# BeoModern_schemat.net
KiCad netlist of a schematic drawn in EAGLE
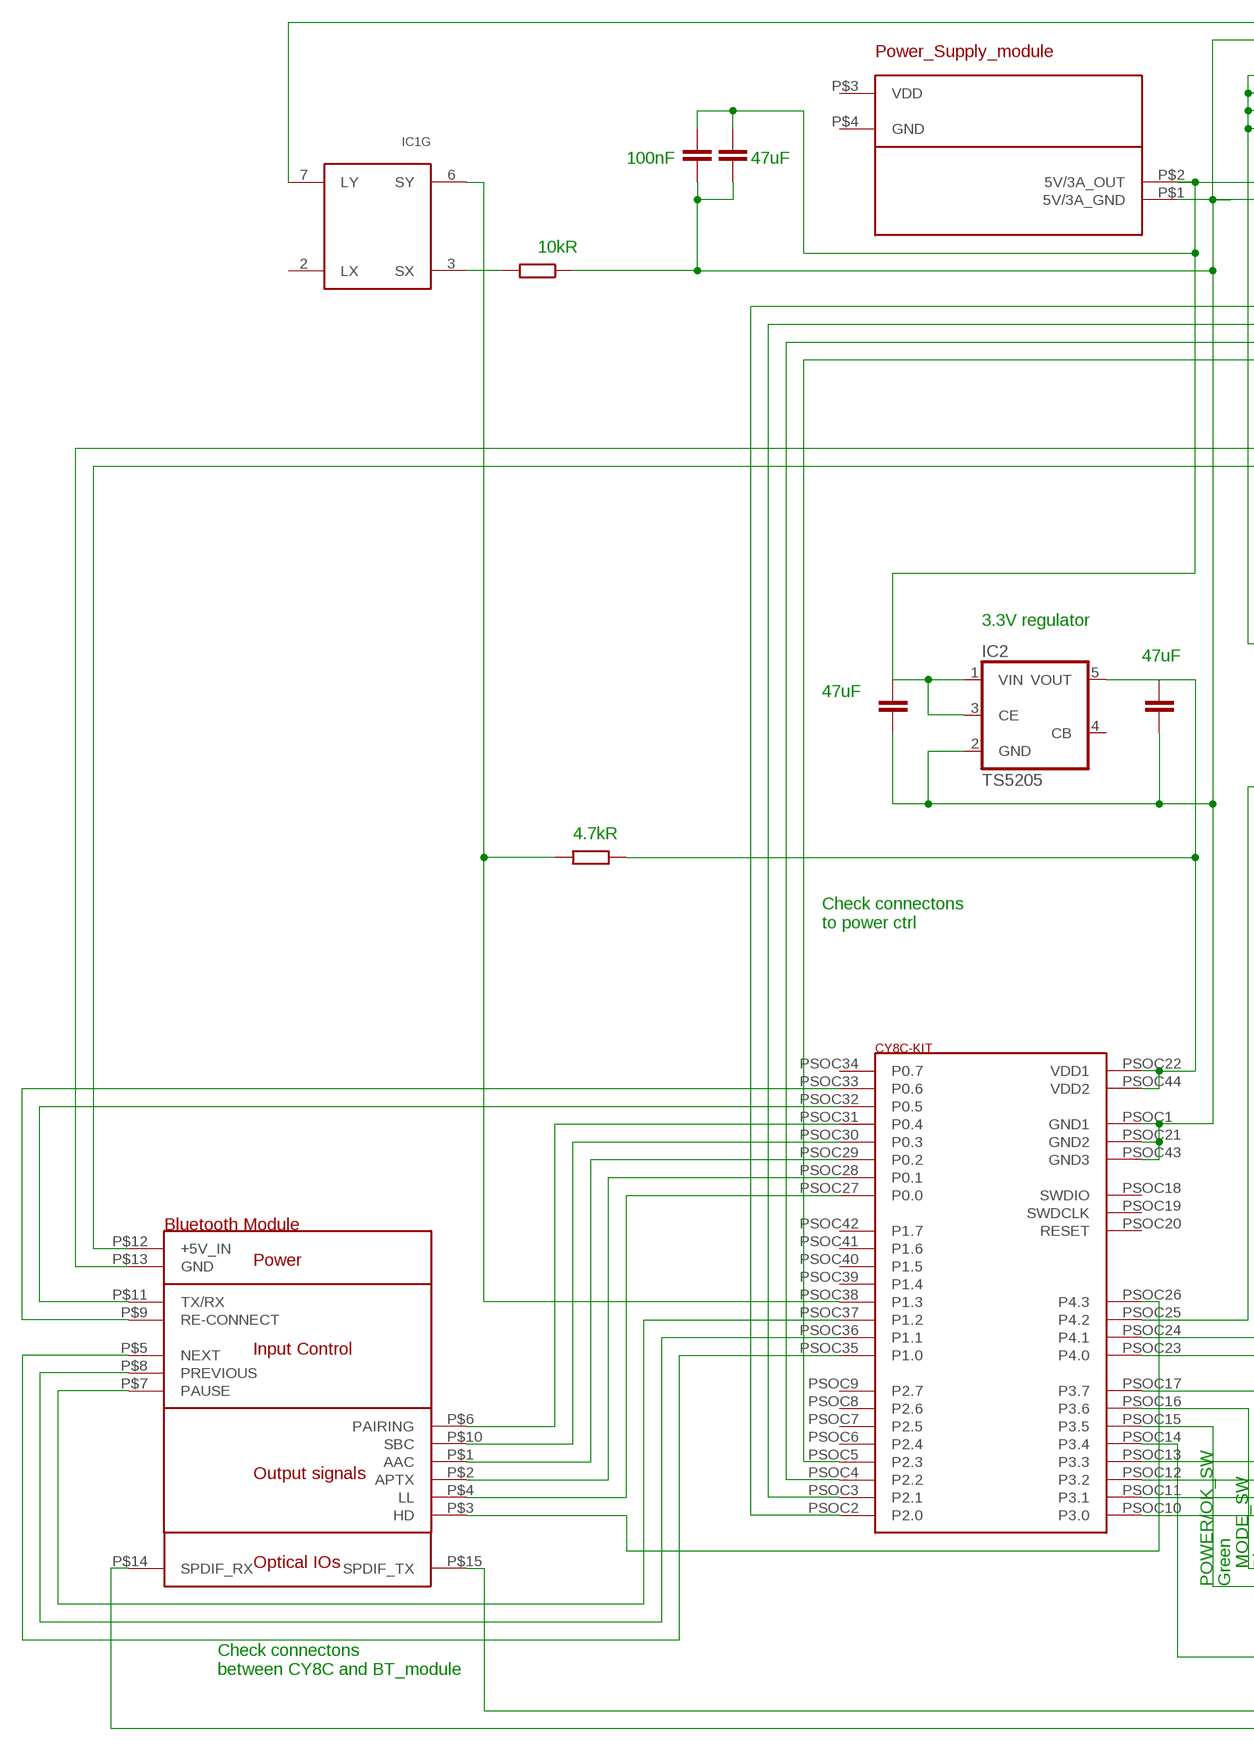
[diagram p0: schematic, sheet 1, part 1 of 2]
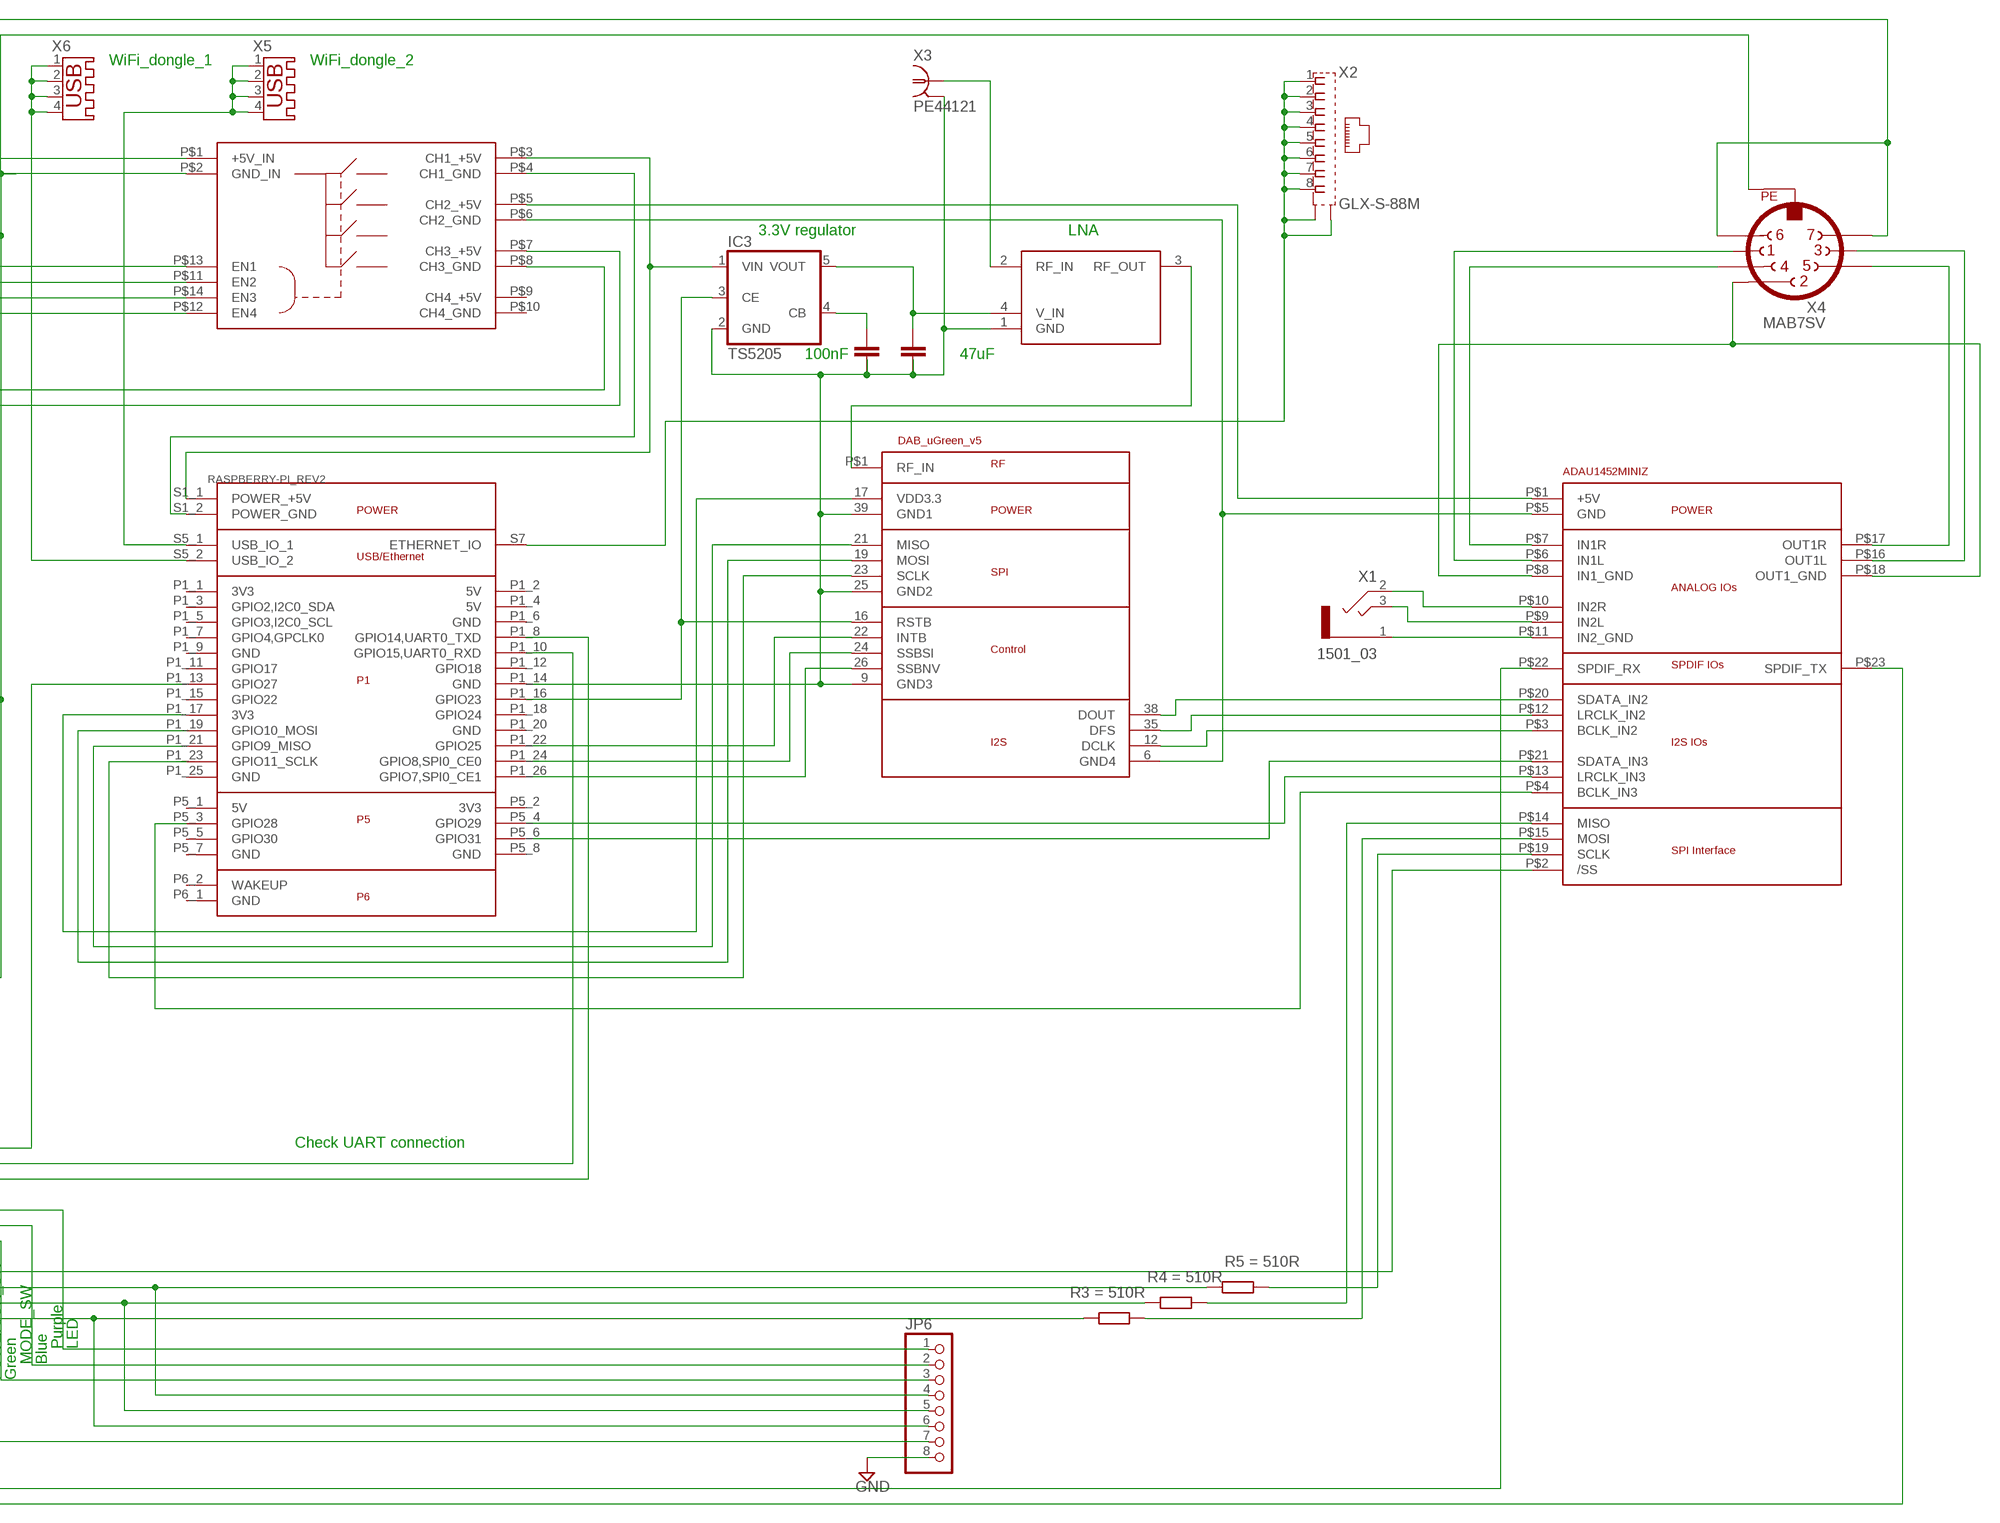
[diagram p1: schematic, sheet 1, part 2 of 2]

(export (version "E")
  (design (tool "Eeschema 10.0.6"))
  (components
    (comp (ref "IC1")
      (value "82B715TD")
      (footprint "eagle-import:SO8")
      (fields (field (name "MPN") "P82B715TD,118"))
      (libsource (lib "eagle-import") (part "82B715TD"))
    )
    (comp (ref "IC2")
      (value "TS5205")
      (footprint "eagle-import:SOT25")
      (libsource (lib "eagle-import") (part "TS5205"))
    )
    (comp (ref "IC3")
      (value "TS5205")
      (footprint "eagle-import:SOT25")
      (libsource (lib "eagle-import") (part "TS5205"))
    )
    (comp (ref "JP6")
      (value "PINHD-1X8")
      (footprint "eagle-import:1X08")
      (libsource (lib "eagle-import") (part "PINHD-1X8"))
    )
    (comp (ref "U$1")
      (value "RASPBERRY-PI_REV2")
      (footprint "eagle-import:RASPBERRY-PI_REV2")
      (libsource (lib "eagle-import") (part "RASPBERRY-PI_REV2"))
    )
    (comp (ref "U$2")
      (value "ADAU1452MINIZ")
      (footprint "eagle-import:ADAU1452MINIZ")
      (libsource (lib "eagle-import") (part "ADAU1452MINIZ"))
    )
    (comp (ref "U$3")
      (value "5V_PSU_MODULE")
      (footprint "eagle-import:5V_PSU_MODULE")
      (libsource (lib "eagle-import") (part "5V_PSU_MODULE"))
    )
    (comp (ref "U$4")
      (value "PSU_SWITCH")
      (footprint "eagle-import:PSU_SWITCH")
      (libsource (lib "eagle-import") (part "PSU_SWITCH"))
    )
    (comp (ref "U$5")
      (value "DAB_UGREEN_V5")
      (footprint "eagle-import:DAB_UGREEN_V5")
      (libsource (lib "eagle-import") (part "DAB_UGREEN_V5"))
    )
    (comp (ref "U$6")
      (value "CY8C-KIT")
      (footprint "eagle-import:CY8C-KIT-FOOTPRINT")
      (libsource (lib "eagle-import") (part "CY8C-KIT"))
    )
    (comp (ref "U$7")
      (value "LNA")
      (footprint "eagle-import:LNA-FOOTPRINT")
      (libsource (lib "eagle-import") (part "LNA"))
    )
    (comp (ref "U$8")
      (value "BT_MODULE")
      (footprint "eagle-import:BT_MODULE_FOOTPRINT")
      (libsource (lib "eagle-import") (part "BT_MODULE"))
    )
    (comp (ref "X1")
      (value "1501_03")
      (footprint "eagle-import:1501_03")
      (libsource (lib "eagle-import") (part "1501_03"))
    )
    (comp (ref "X2")
      (value "GLX-S-88M")
      (footprint "eagle-import:GLX-S-88M")
      (libsource (lib "eagle-import") (part "GLX-S-88M"))
    )
    (comp (ref "X3")
      (value "PE44121")
      (footprint "eagle-import:PE44121")
      (libsource (lib "eagle-import") (part "PE44121"))
    )
    (comp (ref "X4")
      (value "MAB7SV")
      (footprint "eagle-import:MAB7SV")
      (libsource (lib "eagle-import") (part "MAB7SV"))
    )
    (comp (ref "X5")
      (value "USB-A003")
      (footprint "eagle-import:USB-A003")
      (libsource (lib "eagle-import") (part "USB-A003"))
    )
    (comp (ref "X6")
      (value "USB-A003")
      (footprint "eagle-import:USB-A003")
      (libsource (lib "eagle-import") (part "USB-A003"))
    )
  )
  (nets
    (net (code "1") (name "GND") (class "Default")
      (node (ref "JP6") (pin "8") (pinfunction "8_8") (pintype "passive"))
    )
    (net (code "2") (name "Net-(IC1A-LY)") (class "Default")
      (node (ref "IC1") (pin "7") (pinfunction "LY_7") (pintype "bidirectional"))
      (node (ref "X4") (pin "6") (pinfunction "6_6") (pintype "passive"))
      (node (ref "X4") (pin "7") (pinfunction "7_7") (pintype "passive"))
    )
    (net (code "3") (name "Net-(IC1A-SY)") (class "Default")
      (node (ref "IC1") (pin "6") (pinfunction "SY_6") (pintype "bidirectional"))
      (node (ref "U$6") (pin "PSOC38") (pinfunction "P1.3_PSOC38") (pintype "bidirectional"))
    )
    (net (code "4") (name "Net-(IC2-CE)") (class "Default")
      (node (ref "IC2") (pin "1") (pinfunction "VIN_1") (pintype "input"))
      (node (ref "IC2") (pin "3") (pinfunction "CE_3") (pintype "input"))
      (node (ref "U$3") (pin "P$2") (pinfunction "5V/3A_OUT_P$2") (pintype "bidirectional"))
      (node (ref "U$4") (pin "P$1") (pinfunction "+5V_IN_P$1") (pintype "bidirectional"))
    )
    (net (code "5") (name "Net-(IC2-GND)") (class "Default")
      (node (ref "IC2") (pin "2") (pinfunction "GND_2") (pintype "passive"))
      (node (ref "U$3") (pin "P$1") (pinfunction "5V/3A_GND_P$1") (pintype "bidirectional"))
      (node (ref "U$4") (pin "P$2") (pinfunction "GND_IN_P$2") (pintype "bidirectional"))
      (node (ref "U$6") (pin "PSOC1") (pinfunction "GND1_PSOC1") (pintype "bidirectional"))
      (node (ref "U$6") (pin "PSOC21") (pinfunction "GND2_PSOC21") (pintype "bidirectional"))
      (node (ref "U$6") (pin "PSOC43") (pinfunction "GND3_PSOC43") (pintype "bidirectional"))
      (node (ref "X4") (pin "PE") (pinfunction "PE_PE") (pintype "power_in"))
    )
    (net (code "6") (name "Net-(IC2-VOUT)") (class "Default")
      (node (ref "IC2") (pin "5") (pinfunction "VOUT_5") (pintype "passive"))
      (node (ref "U$6") (pin "PSOC22") (pinfunction "VDD1_PSOC22") (pintype "bidirectional"))
      (node (ref "U$6") (pin "PSOC44") (pinfunction "VDD2_PSOC44") (pintype "bidirectional"))
    )
    (net (code "7") (name "Net-(IC3-CE)") (class "Default")
      (node (ref "IC3") (pin "3") (pinfunction "CE_3") (pintype "input"))
      (node (ref "U$1") (pin "P1_16") (pinfunction "GPIO23_P1_16") (pintype "bidirectional"))
      (node (ref "U$5") (pin "16") (pinfunction "RSTB_16") (pintype "bidirectional"))
    )
    (net (code "8") (name "Net-(IC3-GND)") (class "Default")
      (node (ref "IC3") (pin "2") (pinfunction "GND_2") (pintype "passive"))
      (node (ref "U$1") (pin "P1_14") (pinfunction "GND_P1_14") (pintype "bidirectional"))
      (node (ref "U$5") (pin "25") (pinfunction "GND2_25") (pintype "bidirectional"))
      (node (ref "U$5") (pin "39") (pinfunction "GND1_39") (pintype "bidirectional"))
      (node (ref "U$5") (pin "9") (pinfunction "GND3_9") (pintype "bidirectional"))
      (node (ref "U$7") (pin "1") (pinfunction "GND_1") (pintype "bidirectional"))
      (node (ref "X3") (pin "2@1") (pinfunction "2_2@1") (pintype "passive"))
      (node (ref "X3") (pin "2@2") (pinfunction "2_2@2") (pintype "passive"))
      (node (ref "X3") (pin "2@3") (pinfunction "2_2@3") (pintype "passive"))
      (node (ref "X3") (pin "2@4") (pinfunction "2_2@4") (pintype "passive"))
      (node (ref "X3") (pin "2@5") (pinfunction "2_2@5") (pintype "passive"))
      (node (ref "X3") (pin "2@6") (pinfunction "2_2@6") (pintype "passive"))
    )
    (net (code "9") (name "Net-(IC3-VIN)") (class "Default")
      (node (ref "IC3") (pin "1") (pinfunction "VIN_1") (pintype "input"))
      (node (ref "U$1") (pin "S1_1") (pinfunction "POWER_+5V_S1_1") (pintype "bidirectional"))
      (node (ref "U$4") (pin "P$3") (pinfunction "CH1_+5V_P$3") (pintype "bidirectional"))
    )
    (net (code "10") (name "Net-(IC3-VOUT)") (class "Default")
      (node (ref "IC3") (pin "5") (pinfunction "VOUT_5") (pintype "passive"))
      (node (ref "U$7") (pin "4") (pinfunction "V_IN_4") (pintype "bidirectional"))
    )
    (net (code "11") (name "Net-(U$1-ETHERNET_IO)") (class "Default")
      (node (ref "U$1") (pin "S7") (pinfunction "ETHERNET_IO_S7") (pintype "bidirectional"))
      (node (ref "X2") (pin "1") (pinfunction "1_1") (pintype "passive"))
      (node (ref "X2") (pin "2") (pinfunction "2_2") (pintype "passive"))
      (node (ref "X2") (pin "3") (pinfunction "3_3") (pintype "passive"))
      (node (ref "X2") (pin "4") (pinfunction "4_4") (pintype "passive"))
      (node (ref "X2") (pin "5") (pinfunction "5_5") (pintype "passive"))
      (node (ref "X2") (pin "6") (pinfunction "6_6") (pintype "passive"))
      (node (ref "X2") (pin "7") (pinfunction "7_7") (pintype "passive"))
      (node (ref "X2") (pin "8") (pinfunction "8_8") (pintype "passive"))
      (node (ref "X2") (pin "S1") (pinfunction "S1_S1") (pintype "passive"))
      (node (ref "X2") (pin "S2") (pinfunction "S2_S2") (pintype "passive"))
    )
    (net (code "12") (name "Net-(U$1-GPIO7,SPI0_CE1)") (class "Default")
      (node (ref "U$1") (pin "P1_26") (pinfunction "GPIO7,SPI0_CE1_P1_26") (pintype "bidirectional"))
      (node (ref "U$5") (pin "26") (pinfunction "SSBNV_26") (pintype "bidirectional"))
    )
    (net (code "13") (name "Net-(U$1-GPIO8,SPI0_CE0)") (class "Default")
      (node (ref "U$1") (pin "P1_24") (pinfunction "GPIO8,SPI0_CE0_P1_24") (pintype "bidirectional"))
      (node (ref "U$5") (pin "24") (pinfunction "SSBSI_24") (pintype "bidirectional"))
    )
    (net (code "14") (name "Net-(U$1-GPIO9_MISO)") (class "Default")
      (node (ref "U$1") (pin "P1_21") (pinfunction "GPIO9_MISO_P1_21") (pintype "bidirectional"))
      (node (ref "U$5") (pin "21") (pinfunction "MISO_21") (pintype "bidirectional"))
    )
    (net (code "15") (name "Net-(U$1-GPIO10_MOSI)") (class "Default")
      (node (ref "U$1") (pin "P1_19") (pinfunction "GPIO10_MOSI_P1_19") (pintype "bidirectional"))
      (node (ref "U$5") (pin "19") (pinfunction "MOSI_19") (pintype "bidirectional"))
    )
    (net (code "16") (name "Net-(U$1-GPIO11_SCLK)") (class "Default")
      (node (ref "U$1") (pin "P1_23") (pinfunction "GPIO11_SCLK_P1_23") (pintype "bidirectional"))
      (node (ref "U$5") (pin "23") (pinfunction "SCLK_23") (pintype "bidirectional"))
    )
    (net (code "17") (name "Net-(U$1-GPIO14,UART0_TXD)") (class "Default")
      (node (ref "U$1") (pin "P1_8") (pinfunction "GPIO14,UART0_TXD_P1_8") (pintype "bidirectional"))
      (node (ref "U$6") (pin "PSOC23") (pinfunction "P4.0_PSOC23") (pintype "bidirectional"))
    )
    (net (code "18") (name "Net-(U$1-GPIO15,UART0_RXD)") (class "Default")
      (node (ref "U$1") (pin "P1_10") (pinfunction "GPIO15,UART0_RXD_P1_10") (pintype "bidirectional"))
      (node (ref "U$6") (pin "PSOC24") (pinfunction "P4.1_PSOC24") (pintype "bidirectional"))
    )
    (net (code "19") (name "Net-(U$1-GPIO25)") (class "Default")
      (node (ref "U$1") (pin "P1_22") (pinfunction "GPIO25_P1_22") (pintype "bidirectional"))
      (node (ref "U$5") (pin "22") (pinfunction "INTB_22") (pintype "bidirectional"))
    )
    (net (code "20") (name "Net-(U$1-GPIO27)") (class "Default")
      (node (ref "U$1") (pin "P1_13") (pinfunction "GPIO27_P1_13") (pintype "bidirectional"))
      (node (ref "U$6") (pin "PSOC25") (pinfunction "P4.2_PSOC25") (pintype "bidirectional"))
    )
    (net (code "21") (name "Net-(U$1-GPIO28)") (class "Default")
      (node (ref "U$1") (pin "P5_3") (pinfunction "GPIO28_P5_3") (pintype "bidirectional"))
      (node (ref "U$2") (pin "P$4") (pinfunction "BCLK_IN3_P$4") (pintype "bidirectional"))
    )
    (net (code "22") (name "Net-(U$1-GPIO29)") (class "Default")
      (node (ref "U$1") (pin "P5_4") (pinfunction "GPIO29_P5_4") (pintype "bidirectional"))
      (node (ref "U$2") (pin "P$13") (pinfunction "LRCLK_IN3_P$13") (pintype "bidirectional"))
    )
    (net (code "23") (name "Net-(U$1-GPIO31)") (class "Default")
      (node (ref "U$1") (pin "P5_6") (pinfunction "GPIO31_P5_6") (pintype "bidirectional"))
      (node (ref "U$2") (pin "P$21") (pinfunction "SDATA_IN3_P$21") (pintype "bidirectional"))
    )
    (net (code "24") (name "Net-(U$1-POWER_GND)") (class "Default")
      (node (ref "U$1") (pin "S1_2") (pinfunction "POWER_GND_S1_2") (pintype "bidirectional"))
      (node (ref "U$4") (pin "P$4") (pinfunction "CH1_GND_P$4") (pintype "bidirectional"))
    )
    (net (code "25") (name "Net-(U$1-USB_IO_1)") (class "Default")
      (node (ref "U$1") (pin "S5_1") (pinfunction "USB_IO_1_S5_1") (pintype "bidirectional"))
      (node (ref "X5") (pin "1") (pinfunction "1_1") (pintype "passive"))
      (node (ref "X5") (pin "2") (pinfunction "2_2") (pintype "passive"))
      (node (ref "X5") (pin "3") (pinfunction "3_3") (pintype "passive"))
      (node (ref "X5") (pin "4") (pinfunction "4_4") (pintype "passive"))
    )
    (net (code "26") (name "Net-(U$1-USB_IO_2)") (class "Default")
      (node (ref "U$1") (pin "S5_2") (pinfunction "USB_IO_2_S5_2") (pintype "bidirectional"))
      (node (ref "X6") (pin "1") (pinfunction "1_1") (pintype "passive"))
      (node (ref "X6") (pin "2") (pinfunction "2_2") (pintype "passive"))
      (node (ref "X6") (pin "3") (pinfunction "3_3") (pintype "passive"))
      (node (ref "X6") (pin "4") (pinfunction "4_4") (pintype "passive"))
    )
    (net (code "27") (name "Net-(U$2-+5V)") (class "Default")
      (node (ref "U$2") (pin "P$1") (pinfunction "+5V_P$1") (pintype "bidirectional"))
      (node (ref "U$4") (pin "P$5") (pinfunction "CH2_+5V_P$5") (pintype "bidirectional"))
    )
    (net (code "28") (name "Net-(U$2-BCLK_IN2)") (class "Default")
      (node (ref "U$2") (pin "P$3") (pinfunction "BCLK_IN2_P$3") (pintype "bidirectional"))
      (node (ref "U$5") (pin "12") (pinfunction "DCLK_12") (pintype "bidirectional"))
    )
    (net (code "29") (name "Net-(U$2-GND)") (class "Default")
      (node (ref "U$2") (pin "P$5") (pinfunction "GND_P$5") (pintype "bidirectional"))
      (node (ref "U$4") (pin "P$6") (pinfunction "CH2_GND_P$6") (pintype "bidirectional"))
      (node (ref "U$5") (pin "6") (pinfunction "GND4_6") (pintype "bidirectional"))
    )
    (net (code "30") (name "Net-(U$2-IN1L)") (class "Default")
      (node (ref "U$2") (pin "P$6") (pinfunction "IN1L_P$6") (pintype "bidirectional"))
      (node (ref "X4") (pin "1") (pinfunction "1_1") (pintype "passive"))
    )
    (net (code "31") (name "Net-(U$2-IN1R)") (class "Default")
      (node (ref "U$2") (pin "P$7") (pinfunction "IN1R_P$7") (pintype "bidirectional"))
      (node (ref "X4") (pin "4") (pinfunction "4_4") (pintype "passive"))
    )
    (net (code "32") (name "Net-(U$2-IN1_GND)") (class "Default")
      (node (ref "U$2") (pin "P$18") (pinfunction "OUT1_GND_P$18") (pintype "bidirectional"))
      (node (ref "U$2") (pin "P$8") (pinfunction "IN1_GND_P$8") (pintype "bidirectional"))
      (node (ref "X4") (pin "2") (pinfunction "2_2") (pintype "passive"))
    )
    (net (code "33") (name "Net-(U$2-IN2L)") (class "Default")
      (node (ref "U$2") (pin "P$9") (pinfunction "IN2L_P$9") (pintype "bidirectional"))
      (node (ref "X1") (pin "3") (pinfunction "3_3") (pintype "passive"))
    )
    (net (code "34") (name "Net-(U$2-IN2R)") (class "Default")
      (node (ref "U$2") (pin "P$10") (pinfunction "IN2R_P$10") (pintype "bidirectional"))
      (node (ref "X1") (pin "2") (pinfunction "2_2") (pintype "passive"))
    )
    (net (code "35") (name "Net-(U$2-IN2_GND)") (class "Default")
      (node (ref "U$2") (pin "P$11") (pinfunction "IN2_GND_P$11") (pintype "bidirectional"))
      (node (ref "X1") (pin "1") (pinfunction "1_1") (pintype "passive"))
    )
    (net (code "36") (name "Net-(U$2-LRCLK_IN2)") (class "Default")
      (node (ref "U$2") (pin "P$12") (pinfunction "LRCLK_IN2_P$12") (pintype "bidirectional"))
      (node (ref "U$5") (pin "35") (pinfunction "DFS_35") (pintype "bidirectional"))
    )
    (net (code "37") (name "Net-(U$2-OUT1L)") (class "Default")
      (node (ref "U$2") (pin "P$16") (pinfunction "OUT1L_P$16") (pintype "bidirectional"))
      (node (ref "X4") (pin "3") (pinfunction "3_3") (pintype "passive"))
    )
    (net (code "38") (name "Net-(U$2-OUT1R)") (class "Default")
      (node (ref "U$2") (pin "P$17") (pinfunction "OUT1R_P$17") (pintype "bidirectional"))
      (node (ref "X4") (pin "5") (pinfunction "5_5") (pintype "passive"))
    )
    (net (code "39") (name "Net-(U$2-SDATA_IN2)") (class "Default")
      (node (ref "U$2") (pin "P$20") (pinfunction "SDATA_IN2_P$20") (pintype "bidirectional"))
      (node (ref "U$5") (pin "38") (pinfunction "DOUT_38") (pintype "bidirectional"))
    )
    (net (code "40") (name "Net-(U$2-SPDIF_RX)") (class "Default")
      (node (ref "U$2") (pin "P$22") (pinfunction "SPDIF_RX_P$22") (pintype "bidirectional"))
      (node (ref "U$8") (pin "P$15") (pinfunction "SPDIF_TX_P$15") (pintype "bidirectional"))
    )
    (net (code "41") (name "Net-(U$2-SPDIF_TX)") (class "Default")
      (node (ref "U$2") (pin "P$23") (pinfunction "SPDIF_TX_P$23") (pintype "bidirectional"))
      (node (ref "U$8") (pin "P$14") (pinfunction "SPDIF_RX_P$14") (pintype "bidirectional"))
    )
    (net (code "42") (name "Net-(U$2-{slash}SS)") (class "Default")
      (node (ref "U$2") (pin "P$2") (pinfunction "/SS_P$2") (pintype "bidirectional"))
      (node (ref "U$6") (pin "PSOC13") (pinfunction "P3.3_PSOC13") (pintype "bidirectional"))
    )
    (net (code "43") (name "Net-(U$4-CH3_+5V)") (class "Default")
      (node (ref "U$4") (pin "P$7") (pinfunction "CH3_+5V_P$7") (pintype "bidirectional"))
      (node (ref "U$8") (pin "P$12") (pinfunction "+5V_IN_P$12") (pintype "bidirectional"))
    )
    (net (code "44") (name "Net-(U$4-CH3_GND)") (class "Default")
      (node (ref "U$4") (pin "P$8") (pinfunction "CH3_GND_P$8") (pintype "bidirectional"))
      (node (ref "U$8") (pin "P$13") (pinfunction "GND_P$13") (pintype "bidirectional"))
    )
    (net (code "45") (name "Net-(U$4-EN1)") (class "Default")
      (node (ref "U$4") (pin "P$13") (pinfunction "EN1_P$13") (pintype "bidirectional"))
      (node (ref "U$6") (pin "PSOC2") (pinfunction "P2.0_PSOC2") (pintype "bidirectional"))
    )
    (net (code "46") (name "Net-(U$4-EN2)") (class "Default")
      (node (ref "U$4") (pin "P$11") (pinfunction "EN2_P$11") (pintype "bidirectional"))
      (node (ref "U$6") (pin "PSOC3") (pinfunction "P2.1_PSOC3") (pintype "bidirectional"))
    )
    (net (code "47") (name "Net-(U$4-EN3)") (class "Default")
      (node (ref "U$4") (pin "P$14") (pinfunction "EN3_P$14") (pintype "bidirectional"))
      (node (ref "U$6") (pin "PSOC4") (pinfunction "P2.2_PSOC4") (pintype "bidirectional"))
    )
    (net (code "48") (name "Net-(U$4-EN4)") (class "Default")
      (node (ref "U$4") (pin "P$12") (pinfunction "EN4_P$12") (pintype "bidirectional"))
      (node (ref "U$6") (pin "PSOC5") (pinfunction "P2.3_PSOC5") (pintype "bidirectional"))
    )
    (net (code "49") (name "Net-(U$5-RF_IN)") (class "Default")
      (node (ref "U$5") (pin "P$1") (pinfunction "RF_IN_P$1") (pintype "bidirectional"))
      (node (ref "U$7") (pin "3") (pinfunction "RF_OUT_3") (pintype "bidirectional"))
    )
    (net (code "50") (name "Net-(U$5-VDD3.3)") (class "Default")
      (node (ref "U$1") (pin "P1_17") (pinfunction "3V3_P1_17") (pintype "bidirectional"))
      (node (ref "U$5") (pin "17") (pinfunction "VDD3.3_17") (pintype "bidirectional"))
    )
    (net (code "51") (name "Net-(U$6-P0.0)") (class "Default")
      (node (ref "U$6") (pin "PSOC27") (pinfunction "P0.0_PSOC27") (pintype "bidirectional"))
      (node (ref "U$8") (pin "P$4") (pinfunction "LL_P$4") (pintype "bidirectional"))
    )
    (net (code "52") (name "Net-(U$6-P0.1)") (class "Default")
      (node (ref "U$6") (pin "PSOC28") (pinfunction "P0.1_PSOC28") (pintype "bidirectional"))
      (node (ref "U$8") (pin "P$2") (pinfunction "APTX_P$2") (pintype "bidirectional"))
    )
    (net (code "53") (name "Net-(U$6-P0.2)") (class "Default")
      (node (ref "U$6") (pin "PSOC29") (pinfunction "P0.2_PSOC29") (pintype "bidirectional"))
      (node (ref "U$8") (pin "P$1") (pinfunction "AAC_P$1") (pintype "bidirectional"))
    )
    (net (code "54") (name "Net-(U$6-P0.3)") (class "Default")
      (node (ref "U$6") (pin "PSOC30") (pinfunction "P0.3_PSOC30") (pintype "bidirectional"))
      (node (ref "U$8") (pin "P$10") (pinfunction "SBC_P$10") (pintype "bidirectional"))
    )
    (net (code "55") (name "Net-(U$6-P0.4)") (class "Default")
      (node (ref "U$6") (pin "PSOC31") (pinfunction "P0.4_PSOC31") (pintype "bidirectional"))
      (node (ref "U$8") (pin "P$6") (pinfunction "PAIRING_P$6") (pintype "bidirectional"))
    )
    (net (code "56") (name "Net-(U$6-P0.5)") (class "Default")
      (node (ref "U$6") (pin "PSOC32") (pinfunction "P0.5_PSOC32") (pintype "bidirectional"))
      (node (ref "U$8") (pin "P$11") (pinfunction "TX/RX_P$11") (pintype "bidirectional"))
    )
    (net (code "57") (name "Net-(U$6-P0.6)") (class "Default")
      (node (ref "U$6") (pin "PSOC33") (pinfunction "P0.6_PSOC33") (pintype "bidirectional"))
      (node (ref "U$8") (pin "P$9") (pinfunction "RE-CONNECT_P$9") (pintype "bidirectional"))
    )
    (net (code "58") (name "Net-(U$6-P1.0)") (class "Default")
      (node (ref "U$6") (pin "PSOC35") (pinfunction "P1.0_PSOC35") (pintype "bidirectional"))
      (node (ref "U$8") (pin "P$5") (pinfunction "NEXT_P$5") (pintype "bidirectional"))
    )
    (net (code "59") (name "Net-(U$6-P1.1)") (class "Default")
      (node (ref "U$6") (pin "PSOC36") (pinfunction "P1.1_PSOC36") (pintype "bidirectional"))
      (node (ref "U$8") (pin "P$8") (pinfunction "PREVIOUS_P$8") (pintype "bidirectional"))
    )
    (net (code "60") (name "Net-(U$6-P1.2)") (class "Default")
      (node (ref "U$6") (pin "PSOC37") (pinfunction "P1.2_PSOC37") (pintype "bidirectional"))
      (node (ref "U$8") (pin "P$7") (pinfunction "PAUSE_P$7") (pintype "bidirectional"))
    )
    (net (code "61") (name "Net-(U$6-P3.0)") (class "Default")
      (node (ref "JP6") (pin "6") (pinfunction "6_6") (pintype "passive"))
      (node (ref "U$6") (pin "PSOC10") (pinfunction "P3.0_PSOC10") (pintype "bidirectional"))
    )
    (net (code "62") (name "Net-(U$6-P3.1)") (class "Default")
      (node (ref "JP6") (pin "5") (pinfunction "5_5") (pintype "passive"))
      (node (ref "U$6") (pin "PSOC11") (pinfunction "P3.1_PSOC11") (pintype "bidirectional"))
    )
    (net (code "63") (name "Net-(U$6-P3.2)") (class "Default")
      (node (ref "JP6") (pin "4") (pinfunction "4_4") (pintype "passive"))
      (node (ref "U$6") (pin "PSOC12") (pinfunction "P3.2_PSOC12") (pintype "bidirectional"))
    )
    (net (code "64") (name "Net-(U$6-P3.4)") (class "Default")
      (node (ref "JP6") (pin "7") (pinfunction "7_7") (pintype "passive"))
      (node (ref "U$6") (pin "PSOC14") (pinfunction "P3.4_PSOC14") (pintype "bidirectional"))
    )
    (net (code "65") (name "Net-(U$6-P3.5)") (class "Default")
      (node (ref "JP6") (pin "3") (pinfunction "3_3") (pintype "passive"))
      (node (ref "U$6") (pin "PSOC15") (pinfunction "P3.5_PSOC15") (pintype "bidirectional"))
    )
    (net (code "66") (name "Net-(U$6-P3.6)") (class "Default")
      (node (ref "JP6") (pin "2") (pinfunction "2_2") (pintype "passive"))
      (node (ref "U$6") (pin "PSOC16") (pinfunction "P3.6_PSOC16") (pintype "bidirectional"))
    )
    (net (code "67") (name "Net-(U$6-P3.7)") (class "Default")
      (node (ref "JP6") (pin "1") (pinfunction "1_1") (pintype "passive"))
      (node (ref "U$6") (pin "PSOC17") (pinfunction "P3.7_PSOC17") (pintype "bidirectional"))
    )
    (net (code "68") (name "Net-(U$6-P4.3)") (class "Default")
      (node (ref "U$6") (pin "PSOC26") (pinfunction "P4.3_PSOC26") (pintype "bidirectional"))
      (node (ref "U$8") (pin "P$3") (pinfunction "HD_P$3") (pintype "bidirectional"))
    )
    (net (code "69") (name "Net-(U$7-RF_IN)") (class "Default")
      (node (ref "U$7") (pin "2") (pinfunction "RF_IN_2") (pintype "bidirectional"))
      (node (ref "X3") (pin "1") (pinfunction "1_1") (pintype "passive"))
    )
    (net (code "70") (name "unconnected-(IC1A-LX-Pad2)") (class "Default")
      (node (ref "IC1") (pin "2") (pinfunction "LX_2") (pintype "bidirectional"))
    )
    (net (code "71") (name "unconnected-(IC1A-SX-Pad3)") (class "Default")
      (node (ref "IC1") (pin "3") (pinfunction "SX_3") (pintype "bidirectional"))
    )
    (net (code "72") (name "unconnected-(IC2-CB-Pad4)") (class "Default")
      (node (ref "IC2") (pin "4") (pinfunction "CB_4") (pintype "input"))
    )
    (net (code "73") (name "unconnected-(IC3-CB-Pad4)") (class "Default")
      (node (ref "IC3") (pin "4") (pinfunction "CB_4") (pintype "input"))
    )
    (net (code "74") (name "unconnected-(U$1-3V3-PadP1_1)") (class "Default")
      (node (ref "U$1") (pin "P1_1") (pinfunction "3V3_P1_1") (pintype "bidirectional"))
    )
    (net (code "75") (name "unconnected-(U$1-3V3-PadP5_2)") (class "Default")
      (node (ref "U$1") (pin "P5_2") (pinfunction "3V3_P5_2") (pintype "bidirectional"))
    )
    (net (code "76") (name "unconnected-(U$1-5V-PadP1_2)") (class "Default")
      (node (ref "U$1") (pin "P1_2") (pinfunction "5V_P1_2") (pintype "bidirectional"))
    )
    (net (code "77") (name "unconnected-(U$1-5V-PadP1_4)") (class "Default")
      (node (ref "U$1") (pin "P1_4") (pinfunction "5V_P1_4") (pintype "bidirectional"))
    )
    (net (code "78") (name "unconnected-(U$1-5V-PadP5_1)") (class "Default")
      (node (ref "U$1") (pin "P5_1") (pinfunction "5V_P5_1") (pintype "bidirectional"))
    )
    (net (code "79") (name "unconnected-(U$1-GND-PadP1_6)") (class "Default")
      (node (ref "U$1") (pin "P1_6") (pinfunction "GND_P1_6") (pintype "bidirectional"))
    )
    (net (code "80") (name "unconnected-(U$1-GND-PadP1_9)") (class "Default")
      (node (ref "U$1") (pin "P1_9") (pinfunction "GND_P1_9") (pintype "bidirectional"))
    )
    (net (code "81") (name "unconnected-(U$1-GND-PadP1_20)") (class "Default")
      (node (ref "U$1") (pin "P1_20") (pinfunction "GND_P1_20") (pintype "bidirectional"))
    )
    (net (code "82") (name "unconnected-(U$1-GND-PadP1_25)") (class "Default")
      (node (ref "U$1") (pin "P1_25") (pinfunction "GND_P1_25") (pintype "bidirectional"))
    )
    (net (code "83") (name "unconnected-(U$1-GND-PadP5_7)") (class "Default")
      (node (ref "U$1") (pin "P5_7") (pinfunction "GND_P5_7") (pintype "bidirectional"))
    )
    (net (code "84") (name "unconnected-(U$1-GND-PadP5_8)") (class "Default")
      (node (ref "U$1") (pin "P5_8") (pinfunction "GND_P5_8") (pintype "bidirectional"))
    )
    (net (code "85") (name "unconnected-(U$1-GND-PadP6_1)") (class "Default")
      (node (ref "U$1") (pin "P6_1") (pinfunction "GND_P6_1") (pintype "bidirectional"))
    )
    (net (code "86") (name "unconnected-(U$1-GPIO2,I2C0_SDA-PadP1_3)") (class "Default")
      (node (ref "U$1") (pin "P1_3") (pinfunction "GPIO2,I2C0_SDA_P1_3") (pintype "bidirectional"))
    )
    (net (code "87") (name "unconnected-(U$1-GPIO3,I2C0_SCL-PadP1_5)") (class "Default")
      (node (ref "U$1") (pin "P1_5") (pinfunction "GPIO3,I2C0_SCL_P1_5") (pintype "bidirectional"))
    )
    (net (code "88") (name "unconnected-(U$1-GPIO4,GPCLK0-PadP1_7)") (class "Default")
      (node (ref "U$1") (pin "P1_7") (pinfunction "GPIO4,GPCLK0_P1_7") (pintype "bidirectional"))
    )
    (net (code "89") (name "unconnected-(U$1-GPIO17-PadP1_11)") (class "Default")
      (node (ref "U$1") (pin "P1_11") (pinfunction "GPIO17_P1_11") (pintype "bidirectional"))
    )
    (net (code "90") (name "unconnected-(U$1-GPIO18-PadP1_12)") (class "Default")
      (node (ref "U$1") (pin "P1_12") (pinfunction "GPIO18_P1_12") (pintype "bidirectional"))
    )
    (net (code "91") (name "unconnected-(U$1-GPIO22-PadP1_15)") (class "Default")
      (node (ref "U$1") (pin "P1_15") (pinfunction "GPIO22_P1_15") (pintype "bidirectional"))
    )
    (net (code "92") (name "unconnected-(U$1-GPIO24-PadP1_18)") (class "Default")
      (node (ref "U$1") (pin "P1_18") (pinfunction "GPIO24_P1_18") (pintype "bidirectional"))
    )
    (net (code "93") (name "unconnected-(U$1-GPIO30-PadP5_5)") (class "Default")
      (node (ref "U$1") (pin "P5_5") (pinfunction "GPIO30_P5_5") (pintype "bidirectional"))
    )
    (net (code "94") (name "unconnected-(U$1-WAKEUP-PadP6_2)") (class "Default")
      (node (ref "U$1") (pin "P6_2") (pinfunction "WAKEUP_P6_2") (pintype "bidirectional"))
    )
    (net (code "95") (name "unconnected-(U$2-MISO-PadP$14)") (class "Default")
      (node (ref "U$2") (pin "P$14") (pinfunction "MISO_P$14") (pintype "bidirectional"))
    )
    (net (code "96") (name "unconnected-(U$2-MOSI-PadP$15)") (class "Default")
      (node (ref "U$2") (pin "P$15") (pinfunction "MOSI_P$15") (pintype "bidirectional"))
    )
    (net (code "97") (name "unconnected-(U$2-SCLK-PadP$19)") (class "Default")
      (node (ref "U$2") (pin "P$19") (pinfunction "SCLK_P$19") (pintype "bidirectional"))
    )
    (net (code "98") (name "unconnected-(U$3-GND-PadP$4)") (class "Default")
      (node (ref "U$3") (pin "P$4") (pinfunction "GND_P$4") (pintype "bidirectional"))
    )
    (net (code "99") (name "unconnected-(U$3-VDD-PadP$3)") (class "Default")
      (node (ref "U$3") (pin "P$3") (pinfunction "VDD_P$3") (pintype "bidirectional"))
    )
    (net (code "100") (name "unconnected-(U$4-CH4_+5V-PadP$9)") (class "Default")
      (node (ref "U$4") (pin "P$9") (pinfunction "CH4_+5V_P$9") (pintype "bidirectional"))
    )
    (net (code "101") (name "unconnected-(U$4-CH4_GND-PadP$10)") (class "Default")
      (node (ref "U$4") (pin "P$10") (pinfunction "CH4_GND_P$10") (pintype "bidirectional"))
    )
    (net (code "102") (name "unconnected-(U$6-P0.7-PadPSOC34)") (class "Default")
      (node (ref "U$6") (pin "PSOC34") (pinfunction "P0.7_PSOC34") (pintype "bidirectional"))
    )
    (net (code "103") (name "unconnected-(U$6-P1.4-PadPSOC39)") (class "Default")
      (node (ref "U$6") (pin "PSOC39") (pinfunction "P1.4_PSOC39") (pintype "bidirectional"))
    )
    (net (code "104") (name "unconnected-(U$6-P1.5-PadPSOC40)") (class "Default")
      (node (ref "U$6") (pin "PSOC40") (pinfunction "P1.5_PSOC40") (pintype "bidirectional"))
    )
    (net (code "105") (name "unconnected-(U$6-P1.6-PadPSOC41)") (class "Default")
      (node (ref "U$6") (pin "PSOC41") (pinfunction "P1.6_PSOC41") (pintype "bidirectional"))
    )
    (net (code "106") (name "unconnected-(U$6-P1.7-PadPSOC42)") (class "Default")
      (node (ref "U$6") (pin "PSOC42") (pinfunction "P1.7_PSOC42") (pintype "bidirectional"))
    )
    (net (code "107") (name "unconnected-(U$6-P2.4-PadPSOC6)") (class "Default")
      (node (ref "U$6") (pin "PSOC6") (pinfunction "P2.4_PSOC6") (pintype "bidirectional"))
    )
    (net (code "108") (name "unconnected-(U$6-P2.5-PadPSOC7)") (class "Default")
      (node (ref "U$6") (pin "PSOC7") (pinfunction "P2.5_PSOC7") (pintype "bidirectional"))
    )
    (net (code "109") (name "unconnected-(U$6-P2.6-PadPSOC8)") (class "Default")
      (node (ref "U$6") (pin "PSOC8") (pinfunction "P2.6_PSOC8") (pintype "bidirectional"))
    )
    (net (code "110") (name "unconnected-(U$6-P2.7-PadPSOC9)") (class "Default")
      (node (ref "U$6") (pin "PSOC9") (pinfunction "P2.7_PSOC9") (pintype "bidirectional"))
    )
    (net (code "111") (name "unconnected-(U$6-RESET-PadPSOC20)") (class "Default")
      (node (ref "U$6") (pin "PSOC20") (pinfunction "RESET_PSOC20") (pintype "bidirectional"))
    )
    (net (code "112") (name "unconnected-(U$6-SWDCLK-PadPSOC19)") (class "Default")
      (node (ref "U$6") (pin "PSOC19") (pinfunction "SWDCLK_PSOC19") (pintype "bidirectional"))
    )
    (net (code "113") (name "unconnected-(U$6-SWDIO-PadPSOC18)") (class "Default")
      (node (ref "U$6") (pin "PSOC18") (pinfunction "SWDIO_PSOC18") (pintype "bidirectional"))
    )
  )
)
